# MEAS-832M1.net
KiCad netlist of a schematic drawn in EAGLE
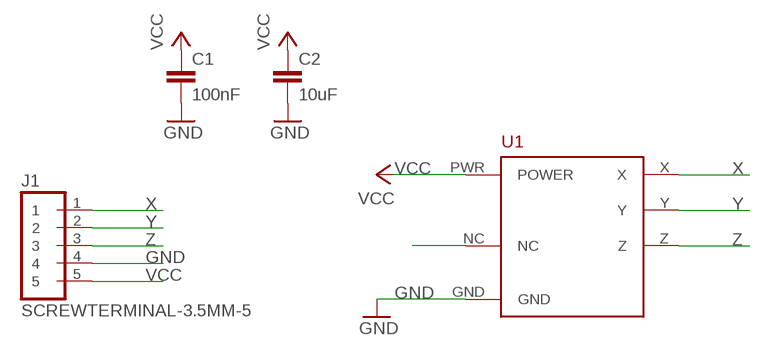
[diagram p0: schematic, sheet 1]

(export (version "E")
  (design (tool "Eeschema 10.0.6"))
  (components
    (comp (ref "C1")
      (value "100nF")
      (footprint "eagle-import:C0805K")
      (libsource (lib "eagle-import") (part "C-EUC0805K"))
    )
    (comp (ref "C2")
      (value "10uF")
      (footprint "eagle-import:C0805K")
      (libsource (lib "eagle-import") (part "C-EUC0805K"))
    )
    (comp (ref "J1")
      (value "SCREWTERMINAL-3.5MM-5")
      (footprint "eagle-import:SCREWTERMINAL-3.5MM-5")
      (libsource (lib "eagle-import") (part "SCREWTERMINAL-3.5MM-5"))
    )
    (comp (ref "U1")
      (value "MEAS-832M1")
      (footprint "eagle-import:MEAS-832M1")
      (libsource (lib "eagle-import") (part "MEAS-832M1"))
    )
  )
  (nets
    (net (code "1") (name "/X") (class "Default")
      (node (ref "J1") (pin "1") (pinfunction "1_1") (pintype "bidirectional"))
      (node (ref "U1") (pin "X") (pinfunction "X_X") (pintype "bidirectional"))
    )
    (net (code "2") (name "/Y") (class "Default")
      (node (ref "J1") (pin "2") (pinfunction "2_2") (pintype "bidirectional"))
      (node (ref "U1") (pin "Y") (pinfunction "Y_Y") (pintype "bidirectional"))
    )
    (net (code "3") (name "/Z") (class "Default")
      (node (ref "J1") (pin "3") (pinfunction "3_3") (pintype "bidirectional"))
      (node (ref "U1") (pin "Z") (pinfunction "Z_Z") (pintype "bidirectional"))
    )
    (net (code "4") (name "GND") (class "Default")
      (node (ref "C1") (pin "2") (pinfunction "2_2") (pintype "passive"))
      (node (ref "C2") (pin "2") (pinfunction "2_2") (pintype "passive"))
      (node (ref "J1") (pin "4") (pinfunction "4_4") (pintype "bidirectional"))
      (node (ref "U1") (pin "GND") (pinfunction "GND_GND") (pintype "bidirectional"))
    )
    (net (code "5") (name "VCC") (class "Default")
      (node (ref "C1") (pin "1") (pinfunction "1_1") (pintype "passive"))
      (node (ref "C2") (pin "1") (pinfunction "1_1") (pintype "passive"))
      (node (ref "J1") (pin "5") (pinfunction "5_5") (pintype "bidirectional"))
      (node (ref "U1") (pin "PWR") (pinfunction "POWER_PWR") (pintype "bidirectional"))
    )
    (net (code "6") (name "unconnected-(U1-PadNC)") (class "Default")
      (node (ref "U1") (pin "NC") (pinfunction "NC_NC") (pintype "bidirectional"))
    )
  )
)
